# Error_Correcting_For_7bit_Hamming_Code.net
KiCad netlist of a schematic drawn in Altium Designer
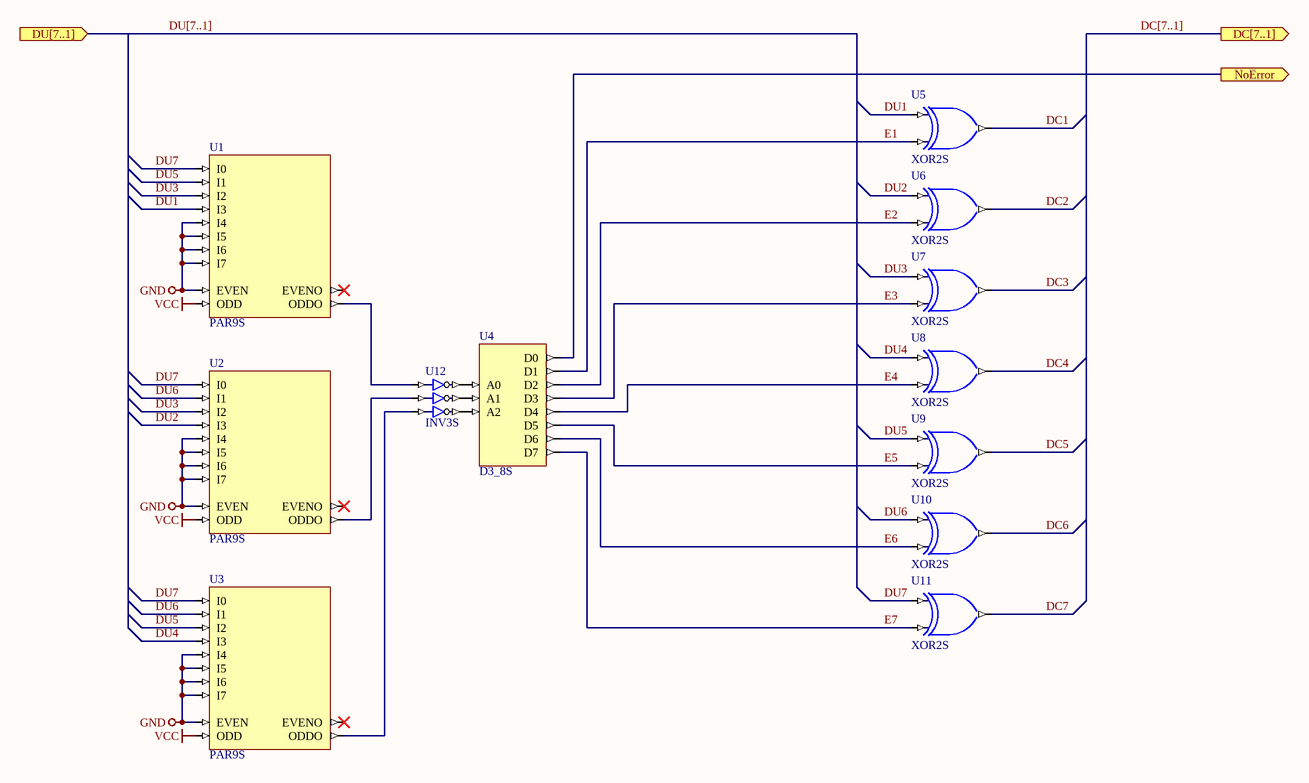
[diagram p0: Error Correcting For 7bit Hamming Code.SchDoc]

(export (version "E")
  (design (tool "Eeschema 10.0.6"))
  (components
    (comp (ref "U1")
      (value "PAR9S")
      (description "9-Bit Odd/Even Parity Generators/Checker, Single Pin Version")
      (fields (field (name "PUBLISHER") "Altium Limited"))
      (libsource (lib "FPGA Generic") (part "PAR9S"))
    )
    (comp (ref "U2")
      (value "PAR9S")
      (description "9-Bit Odd/Even Parity Generators/Checker, Single Pin Version")
      (fields (field (name "PUBLISHER") "Altium Limited"))
      (libsource (lib "FPGA Generic") (part "PAR9S"))
    )
    (comp (ref "U3")
      (value "PAR9S")
      (description "9-Bit Odd/Even Parity Generators/Checker, Single Pin Version")
      (fields (field (name "PUBLISHER") "Altium Limited"))
      (libsource (lib "FPGA Generic") (part "PAR9S"))
    )
    (comp (ref "U4")
      (value "D3_8S")
      (description "Binary 3- to 8-Bit Decoder, Single Pin Version")
      (fields (field (name "PUBLISHER") "Altium Limited"))
      (libsource (lib "FPGA Generic") (part "D3_8S"))
    )
    (comp (ref "U5")
      (value "XOR2S")
      (description "2-Input Exclusive-OR Gate, Single Pin Version")
      (fields (field (name "PUBLISHER") "Altium Limited"))
      (libsource (lib "FPGA Generic") (part "XOR2S"))
    )
    (comp (ref "U6")
      (value "XOR2S")
      (description "2-Input Exclusive-OR Gate, Single Pin Version")
      (fields (field (name "PUBLISHER") "Altium Limited"))
      (libsource (lib "FPGA Generic") (part "XOR2S"))
    )
    (comp (ref "U7")
      (value "XOR2S")
      (description "2-Input Exclusive-OR Gate, Single Pin Version")
      (fields (field (name "PUBLISHER") "Altium Limited"))
      (libsource (lib "FPGA Generic") (part "XOR2S"))
    )
    (comp (ref "U8")
      (value "XOR2S")
      (description "2-Input Exclusive-OR Gate, Single Pin Version")
      (fields (field (name "PUBLISHER") "Altium Limited"))
      (libsource (lib "FPGA Generic") (part "XOR2S"))
    )
    (comp (ref "U9")
      (value "XOR2S")
      (description "2-Input Exclusive-OR Gate, Single Pin Version")
      (fields (field (name "PUBLISHER") "Altium Limited"))
      (libsource (lib "FPGA Generic") (part "XOR2S"))
    )
    (comp (ref "U10")
      (value "XOR2S")
      (description "2-Input Exclusive-OR Gate, Single Pin Version")
      (fields (field (name "PUBLISHER") "Altium Limited"))
      (libsource (lib "FPGA Generic") (part "XOR2S"))
    )
    (comp (ref "U11")
      (value "XOR2S")
      (description "2-Input Exclusive-OR Gate, Single Pin Version")
      (fields (field (name "PUBLISHER") "Altium Limited"))
      (libsource (lib "FPGA Generic") (part "XOR2S"))
    )
    (comp (ref "U12")
      (value "INV3S")
      (description "3-Bit Inverter, Single Pin Version")
      (fields (field (name "PUBLISHER") "Altium Limited"))
      (libsource (lib "FPGA Generic") (part "INV3S"))
    )
  )
  (nets
    (net (code "1") (name "/DC1") (class "Default")
      (node (ref "U5") (pin "O") (pinfunction "O_O") (pintype "output"))
    )
    (net (code "2") (name "/DC2") (class "Default")
      (node (ref "U6") (pin "O") (pinfunction "O_O") (pintype "output"))
    )
    (net (code "3") (name "/DC3") (class "Default")
      (node (ref "U7") (pin "O") (pinfunction "O_O") (pintype "output"))
    )
    (net (code "4") (name "/DC4") (class "Default")
      (node (ref "U8") (pin "O") (pinfunction "O_O") (pintype "output"))
    )
    (net (code "5") (name "/DC5") (class "Default")
      (node (ref "U9") (pin "O") (pinfunction "O_O") (pintype "output"))
    )
    (net (code "6") (name "/DC6") (class "Default")
      (node (ref "U10") (pin "O") (pinfunction "O_O") (pintype "output"))
    )
    (net (code "7") (name "/DC7") (class "Default")
      (node (ref "U11") (pin "O") (pinfunction "O_O") (pintype "output"))
    )
    (net (code "9") (name "/DU1") (class "Default")
      (node (ref "U1") (pin "I3") (pinfunction "I3_I3") (pintype "input"))
      (node (ref "U5") (pin "I0") (pinfunction "I0_I0") (pintype "input"))
    )
    (net (code "10") (name "/DU2") (class "Default")
      (node (ref "U2") (pin "I3") (pinfunction "I3_I3") (pintype "input"))
      (node (ref "U6") (pin "I0") (pinfunction "I0_I0") (pintype "input"))
    )
    (net (code "11") (name "/DU3") (class "Default")
      (node (ref "U1") (pin "I2") (pinfunction "I2_I2") (pintype "input"))
      (node (ref "U2") (pin "I2") (pinfunction "I2_I2") (pintype "input"))
      (node (ref "U7") (pin "I0") (pinfunction "I0_I0") (pintype "input"))
    )
    (net (code "12") (name "/DU4") (class "Default")
      (node (ref "U3") (pin "I3") (pinfunction "I3_I3") (pintype "input"))
      (node (ref "U8") (pin "I0") (pinfunction "I0_I0") (pintype "input"))
    )
    (net (code "13") (name "/DU5") (class "Default")
      (node (ref "U1") (pin "I1") (pinfunction "I1_I1") (pintype "input"))
      (node (ref "U3") (pin "I2") (pinfunction "I2_I2") (pintype "input"))
      (node (ref "U9") (pin "I0") (pinfunction "I0_I0") (pintype "input"))
    )
    (net (code "14") (name "/DU6") (class "Default")
      (node (ref "U10") (pin "I0") (pinfunction "I0_I0") (pintype "input"))
      (node (ref "U2") (pin "I1") (pinfunction "I1_I1") (pintype "input"))
      (node (ref "U3") (pin "I1") (pinfunction "I1_I1") (pintype "input"))
    )
    (net (code "15") (name "/DU7") (class "Default")
      (node (ref "U1") (pin "I0") (pinfunction "I0_I0") (pintype "input"))
      (node (ref "U11") (pin "I0") (pinfunction "I0_I0") (pintype "input"))
      (node (ref "U2") (pin "I0") (pinfunction "I0_I0") (pintype "input"))
      (node (ref "U3") (pin "I0") (pinfunction "I0_I0") (pintype "input"))
    )
    (net (code "17") (name "/E1") (class "Default")
      (node (ref "U4") (pin "D1") (pinfunction "D1_D1") (pintype "output"))
      (node (ref "U5") (pin "I1") (pinfunction "I1_I1") (pintype "input"))
    )
    (net (code "18") (name "/E2") (class "Default")
      (node (ref "U4") (pin "D2") (pinfunction "D2_D2") (pintype "output"))
      (node (ref "U6") (pin "I1") (pinfunction "I1_I1") (pintype "input"))
    )
    (net (code "19") (name "/E3") (class "Default")
      (node (ref "U4") (pin "D3") (pinfunction "D3_D3") (pintype "output"))
      (node (ref "U7") (pin "I1") (pinfunction "I1_I1") (pintype "input"))
    )
    (net (code "20") (name "/E4") (class "Default")
      (node (ref "U4") (pin "D4") (pinfunction "D4_D4") (pintype "output"))
      (node (ref "U8") (pin "I1") (pinfunction "I1_I1") (pintype "input"))
    )
    (net (code "21") (name "/E5") (class "Default")
      (node (ref "U4") (pin "D5") (pinfunction "D5_D5") (pintype "output"))
      (node (ref "U9") (pin "I1") (pinfunction "I1_I1") (pintype "input"))
    )
    (net (code "22") (name "/E6") (class "Default")
      (node (ref "U10") (pin "I1") (pinfunction "I1_I1") (pintype "input"))
      (node (ref "U4") (pin "D6") (pinfunction "D6_D6") (pintype "output"))
    )
    (net (code "23") (name "/E7") (class "Default")
      (node (ref "U11") (pin "I1") (pinfunction "I1_I1") (pintype "input"))
      (node (ref "U4") (pin "D7") (pinfunction "D7_D7") (pintype "output"))
    )
    (net (code "24") (name "/NoError") (class "Default")
      (node (ref "U4") (pin "D0") (pinfunction "D0_D0") (pintype "output"))
    )
    (net (code "25") (name "GND") (class "Default")
      (node (ref "U1") (pin "EVEN") (pinfunction "EVEN_EVEN") (pintype "input"))
      (node (ref "U1") (pin "I4") (pinfunction "I4_I4") (pintype "input"))
      (node (ref "U1") (pin "I5") (pinfunction "I5_I5") (pintype "input"))
      (node (ref "U1") (pin "I6") (pinfunction "I6_I6") (pintype "input"))
      (node (ref "U1") (pin "I7") (pinfunction "I7_I7") (pintype "input"))
      (node (ref "U2") (pin "EVEN") (pinfunction "EVEN_EVEN") (pintype "input"))
      (node (ref "U2") (pin "I4") (pinfunction "I4_I4") (pintype "input"))
      (node (ref "U2") (pin "I5") (pinfunction "I5_I5") (pintype "input"))
      (node (ref "U2") (pin "I6") (pinfunction "I6_I6") (pintype "input"))
      (node (ref "U2") (pin "I7") (pinfunction "I7_I7") (pintype "input"))
      (node (ref "U3") (pin "EVEN") (pinfunction "EVEN_EVEN") (pintype "input"))
      (node (ref "U3") (pin "I4") (pinfunction "I4_I4") (pintype "input"))
      (node (ref "U3") (pin "I5") (pinfunction "I5_I5") (pintype "input"))
      (node (ref "U3") (pin "I6") (pinfunction "I6_I6") (pintype "input"))
      (node (ref "U3") (pin "I7") (pinfunction "I7_I7") (pintype "input"))
    )
    (net (code "26") (name "Net-(U1-PadODDO)") (class "Default")
      (node (ref "U1") (pin "ODDO") (pinfunction "ODDO_ODDO") (pintype "output"))
      (node (ref "U12") (pin "I0") (pinfunction "I0_I0") (pintype "input"))
    )
    (net (code "27") (name "Net-(U12-PadI1)") (class "Default")
      (node (ref "U12") (pin "I1") (pinfunction "I1_I1") (pintype "input"))
      (node (ref "U2") (pin "ODDO") (pinfunction "ODDO_ODDO") (pintype "output"))
    )
    (net (code "28") (name "Net-(U12-PadI2)") (class "Default")
      (node (ref "U12") (pin "I2") (pinfunction "I2_I2") (pintype "input"))
      (node (ref "U3") (pin "ODDO") (pinfunction "ODDO_ODDO") (pintype "output"))
    )
    (net (code "29") (name "Net-(U12-PadO0)") (class "Default")
      (node (ref "U12") (pin "O0") (pinfunction "O0_O0") (pintype "output"))
      (node (ref "U4") (pin "A0") (pinfunction "A0_A0") (pintype "input"))
    )
    (net (code "30") (name "Net-(U12-PadO1)") (class "Default")
      (node (ref "U12") (pin "O1") (pinfunction "O1_O1") (pintype "output"))
      (node (ref "U4") (pin "A1") (pinfunction "A1_A1") (pintype "input"))
    )
    (net (code "31") (name "Net-(U12-PadO2)") (class "Default")
      (node (ref "U12") (pin "O2") (pinfunction "O2_O2") (pintype "output"))
      (node (ref "U4") (pin "A2") (pinfunction "A2_A2") (pintype "input"))
    )
    (net (code "32") (name "VCC") (class "Default")
      (node (ref "U1") (pin "ODD") (pinfunction "ODD_ODD") (pintype "input"))
      (node (ref "U2") (pin "ODD") (pinfunction "ODD_ODD") (pintype "input"))
      (node (ref "U3") (pin "ODD") (pinfunction "ODD_ODD") (pintype "input"))
    )
    (net (code "33") (name "unconnected-(U1-PadEVENO)") (class "Default")
      (node (ref "U1") (pin "EVENO") (pinfunction "EVENO_EVENO") (pintype "output+no_connect"))
    )
    (net (code "34") (name "unconnected-(U2-PadEVENO)") (class "Default")
      (node (ref "U2") (pin "EVENO") (pinfunction "EVENO_EVENO") (pintype "output+no_connect"))
    )
    (net (code "35") (name "unconnected-(U3-PadEVENO)") (class "Default")
      (node (ref "U3") (pin "EVENO") (pinfunction "EVENO_EVENO") (pintype "output+no_connect"))
    )
  )
)
